# MiniAdd-OnV10.net
KiCad netlist of a schematic drawn in EAGLE
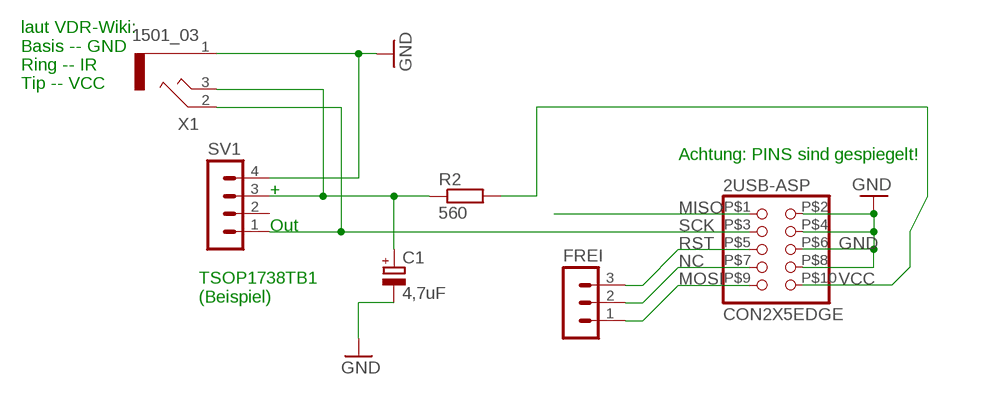
[diagram p0: schematic, sheet 1]

(export (version "E")
  (design (tool "Eeschema 10.0.6"))
  (components
    (comp (ref "2USB-ASP")
      (value "CON2X5EDGE")
      (footprint "eagle-import:CON2X5EDGE")
      (libsource (lib "eagle-import") (part "CON2X5EDGE"))
    )
    (comp (ref "C1")
      (value "4,7uF")
      (footprint "eagle-import:E1,8-4")
      (libsource (lib "eagle-import") (part "CPOL-EUE1.8-4"))
    )
    (comp (ref "FREI")
      (value "MA03-1")
      (footprint "eagle-import:MA03-1")
      (libsource (lib "eagle-import") (part "MA03-1"))
    )
    (comp (ref "R2")
      (value "560")
      (footprint "eagle-import:0204V")
      (libsource (lib "eagle-import") (part "R-EU_0204/2V"))
    )
    (comp (ref "SV1")
      (value "MA04-1")
      (footprint "eagle-import:MA04-1")
      (libsource (lib "eagle-import") (part "MA04-1"))
    )
    (comp (ref "X1")
      (value "1501_03")
      (footprint "eagle-import:1501_03")
      (libsource (lib "eagle-import") (part "1501_03"))
    )
  )
  (nets
    (net (code "1") (name "/MISO") (class "Default")
      (node (ref "2USB-ASP") (pin "P$1") (pinfunction "1_P$1") (pintype "passive"))
    )
    (net (code "2") (name "/MOSI") (class "Default")
      (node (ref "2USB-ASP") (pin "P$9") (pinfunction "9_P$9") (pintype "passive"))
      (node (ref "FREI") (pin "1") (pinfunction "1_1") (pintype "passive"))
    )
    (net (code "3") (name "/NC") (class "Default")
      (node (ref "2USB-ASP") (pin "P$7") (pinfunction "7_P$7") (pintype "passive"))
      (node (ref "FREI") (pin "2") (pinfunction "2_2") (pintype "passive"))
    )
    (net (code "4") (name "/RST") (class "Default")
      (node (ref "2USB-ASP") (pin "P$5") (pinfunction "5_P$5") (pintype "passive"))
      (node (ref "FREI") (pin "3") (pinfunction "3_3") (pintype "passive"))
    )
    (net (code "5") (name "/SCK") (class "Default")
      (node (ref "2USB-ASP") (pin "P$3") (pinfunction "3_P$3") (pintype "passive"))
      (node (ref "SV1") (pin "1") (pinfunction "1_1") (pintype "passive"))
      (node (ref "X1") (pin "2") (pinfunction "2_2") (pintype "passive"))
    )
    (net (code "6") (name "/VCC") (class "Default")
      (node (ref "2USB-ASP") (pin "P$10") (pinfunction "10_P$10") (pintype "passive"))
      (node (ref "R2") (pin "2") (pinfunction "2_2") (pintype "passive"))
    )
    (net (code "7") (name "GND") (class "Default")
      (node (ref "2USB-ASP") (pin "P$2") (pinfunction "2_P$2") (pintype "passive"))
      (node (ref "2USB-ASP") (pin "P$4") (pinfunction "4_P$4") (pintype "passive"))
      (node (ref "2USB-ASP") (pin "P$6") (pinfunction "6_P$6") (pintype "passive"))
      (node (ref "2USB-ASP") (pin "P$8") (pinfunction "8_P$8") (pintype "passive"))
      (node (ref "C1") (pin "-") (pinfunction "-_-") (pintype "passive"))
      (node (ref "SV1") (pin "4") (pinfunction "4_4") (pintype "passive"))
      (node (ref "X1") (pin "1") (pinfunction "1_1") (pintype "passive"))
    )
    (net (code "8") (name "Net-(C1-Pad+)") (class "Default")
      (node (ref "C1") (pin "+") (pinfunction "+_+") (pintype "passive"))
      (node (ref "R2") (pin "1") (pinfunction "1_1") (pintype "passive"))
      (node (ref "SV1") (pin "3") (pinfunction "3_3") (pintype "passive"))
      (node (ref "X1") (pin "3") (pinfunction "3_3") (pintype "passive"))
    )
    (net (code "9") (name "unconnected-(SV1-Pad2)") (class "Default")
      (node (ref "SV1") (pin "2") (pinfunction "2_2") (pintype "passive"))
    )
  )
)
